# EasyEDA_export.net
KiCad netlist of a schematic drawn in EasyEDA
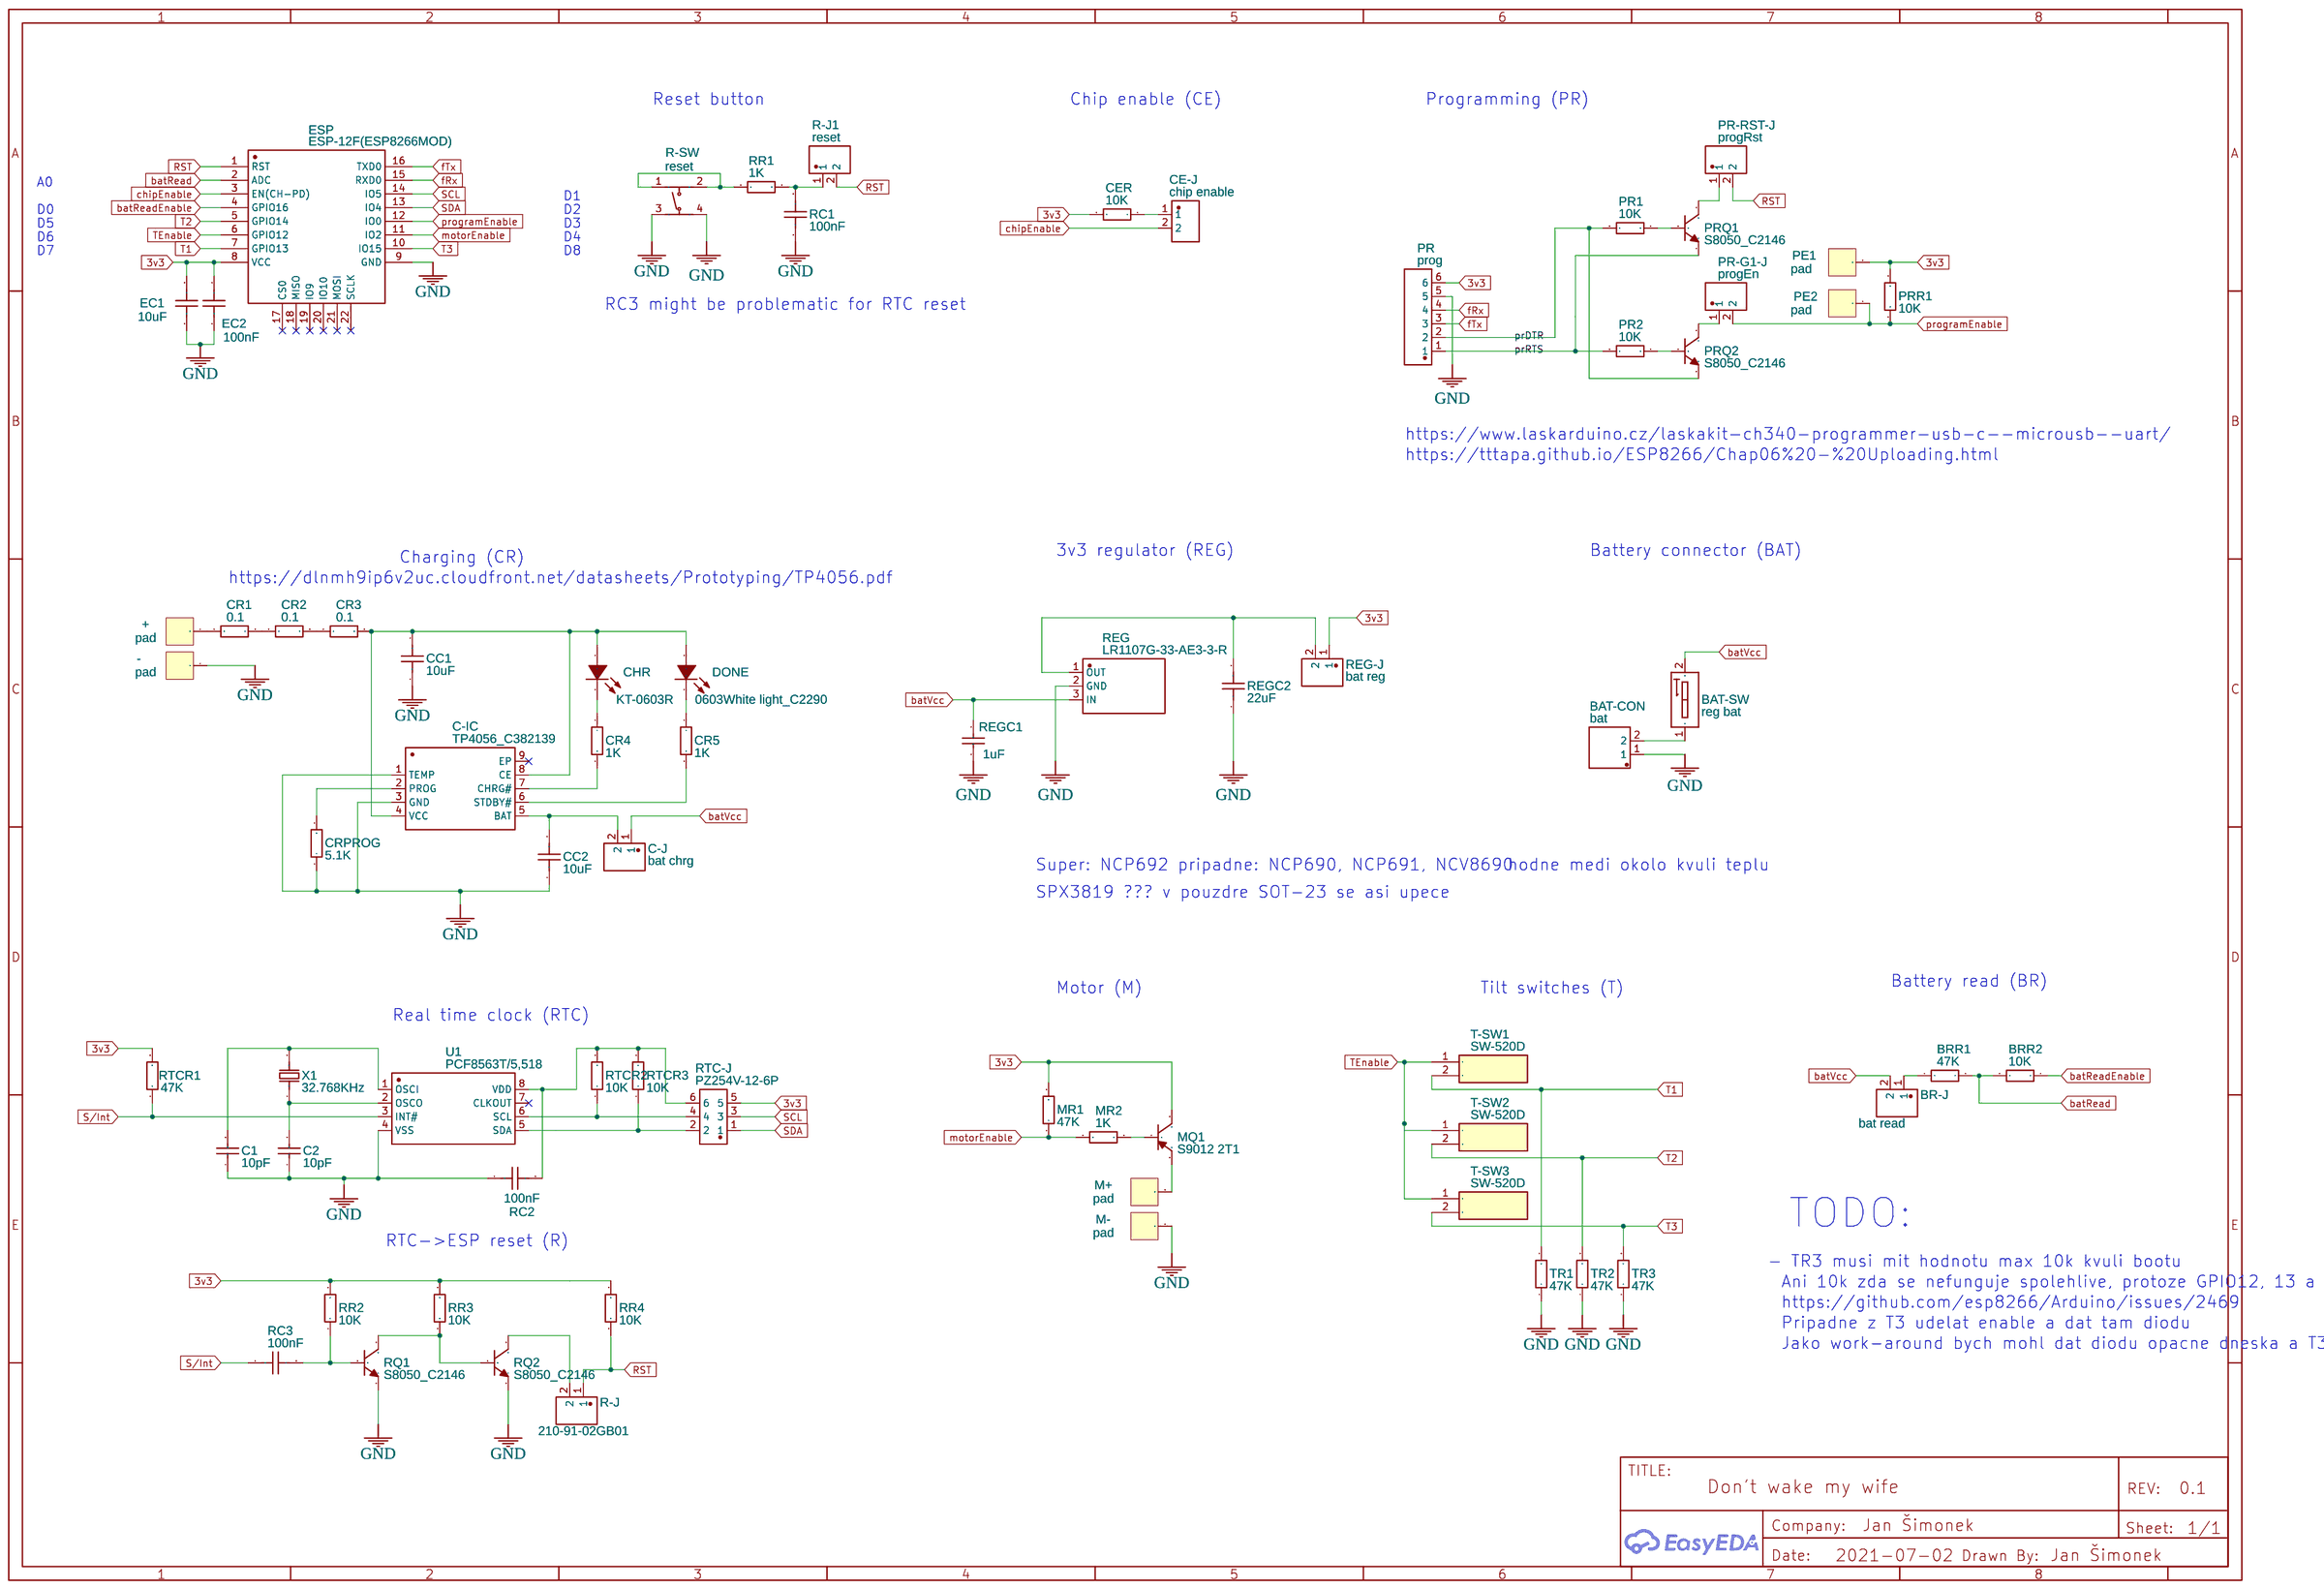
[diagram p0: schematic sheet]

(export (version "E")
  (design (tool "Eeschema 10.0.6"))
  (components
    (comp (ref "+") (value "pad") (libsource (lib "") (part "pad")))
    (comp (ref "-") (value "pad") (libsource (lib "") (part "pad_4")))
    (comp (ref "BAT-CON")
      (value "bat")
      (fields
        (field (name "BOM_Manufacturer Part") "S2B-XH-A-(LF)(SN)")
        (field (name "BOM_Supplier Part") "C157931")
      )
      (libsource (lib "") (part "S2B-XH-A-(LF)(SN)"))
    )
    (comp (ref "BAT-SW")
      (value "reg bat")
      (fields
        (field (name "BOM_Manufacturer Part") "DSIC01LSGET")
        (field (name "BOM_Supplier Part") "C54948")
      )
      (libsource (lib "") (part "DSIC01LSGET"))
    )
    (comp (ref "BR-J")
      (value "bat read")
      (fields
        (field (name "BOM_Manufacturer Part") "210-91-02GB01")
        (field (name "BOM_Supplier Part") "C390678")
      )
      (libsource (lib "") (part "210-91-02GB01"))
    )
    (comp (ref "BRR1")
      (value "47K")
      (fields
        (field (name "BOM_Manufacturer Part") "0603WAF4702T5E")
        (field (name "BOM_Supplier Part") "C25819")
      )
      (libsource (lib "") (part "0603WAF4702T5E_2"))
    )
    (comp (ref "BRR2")
      (value "10K")
      (fields
        (field (name "BOM_Manufacturer Part") "0603WAF1002T5E")
        (field (name "BOM_Supplier Part") "C25804")
      )
      (libsource (lib "") (part "0603WAF1002T5E_2"))
    )
    (comp (ref "C-IC")
      (value "TP4056_C382139")
      (fields (field (name "BOM_Manufacturer Part") "TP4056") (field (name "BOM_Supplier Part") "C382139"))
      (libsource (lib "") (part "TP4056_C382139"))
    )
    (comp (ref "C-J")
      (value "bat chrg")
      (fields
        (field (name "BOM_Manufacturer Part") "210-91-02GB01")
        (field (name "BOM_Supplier Part") "C390678")
      )
      (libsource (lib "") (part "210-91-02GB01_3"))
    )
    (comp (ref "C1")
      (value "10pF")
      (fields
        (field (name "BOM_Manufacturer Part") "CL10C100JB8NNNC")
        (field (name "BOM_Supplier Part") "C1634")
      )
      (libsource (lib "") (part "CL10C100JB8NNNC"))
    )
    (comp (ref "C2")
      (value "10pF")
      (fields
        (field (name "BOM_Manufacturer Part") "CL10C100JB8NNNC")
        (field (name "BOM_Supplier Part") "C1634")
      )
      (libsource (lib "") (part "CL10C100JB8NNNC"))
    )
    (comp (ref "CC1")
      (value "10uF")
      (fields
        (field (name "BOM_Manufacturer Part") "CL10A106KP8NNNC")
        (field (name "BOM_Supplier Part") "C19702")
      )
      (libsource (lib "") (part "CL10A106KP8NNNC_1"))
    )
    (comp (ref "CC2")
      (value "10uF")
      (fields
        (field (name "BOM_Manufacturer Part") "CL10A106KP8NNNC")
        (field (name "BOM_Supplier Part") "C19702")
      )
      (libsource (lib "") (part "CL10A106KP8NNNC_1"))
    )
    (comp (ref "CE-J")
      (value "chip enable")
      (fields
        (field (name "BOM_Manufacturer Part") "210-91-02GB01")
        (field (name "BOM_Supplier Part") "C390678")
      )
      (libsource (lib "") (part "210-91-02GB01_5"))
    )
    (comp (ref "CER")
      (value "10K")
      (fields
        (field (name "BOM_Manufacturer Part") "0603WAF1002T5E")
        (field (name "BOM_Supplier Part") "C25804")
      )
      (libsource (lib "") (part "0603WAF1002T5E_4"))
    )
    (comp (ref "CHR")
      (value "KT-0603R")
      (fields (field (name "BOM_Supplier Part") "C2286"))
      (libsource (lib "") (part "KT-0603R"))
    )
    (comp (ref "CR1")
      (value "0.1")
      (fields
        (field (name "BOM_Manufacturer Part") "0603WAJ010KT5E")
        (field (name "BOM_Supplier Part") "C247025")
      )
      (libsource (lib "") (part "0603WAJ010KT5E"))
    )
    (comp (ref "CR2")
      (value "0.1")
      (fields
        (field (name "BOM_Manufacturer Part") "0603WAJ010KT5E")
        (field (name "BOM_Supplier Part") "C247025")
      )
      (libsource (lib "") (part "0603WAJ010KT5E"))
    )
    (comp (ref "CR3")
      (value "0.1")
      (fields
        (field (name "BOM_Manufacturer Part") "0603WAJ010KT5E")
        (field (name "BOM_Supplier Part") "C247025")
      )
      (libsource (lib "") (part "0603WAJ010KT5E"))
    )
    (comp (ref "CR4")
      (value "1K")
      (fields
        (field (name "BOM_Manufacturer Part") "0603WAF1001T5E")
        (field (name "BOM_Supplier Part") "C21190")
      )
      (libsource (lib "") (part "0603WAF1001T5E"))
    )
    (comp (ref "CR5")
      (value "1K")
      (fields
        (field (name "BOM_Manufacturer Part") "0603WAF1001T5E")
        (field (name "BOM_Supplier Part") "C21190")
      )
      (libsource (lib "") (part "0603WAF1001T5E"))
    )
    (comp (ref "CRPROG")
      (value "5.1K")
      (fields
        (field (name "BOM_Manufacturer Part") "0603WAF5101T5E")
        (field (name "BOM_Supplier Part") "C23186")
      )
      (libsource (lib "") (part "0603WAF5101T5E"))
    )
    (comp (ref "DONE")
      (value "0603White light_C2290")
      (fields
        (field (name "BOM_Manufacturer Part") "0603White light")
        (field (name "BOM_Supplier Part") "C2290")
      )
      (libsource (lib "") (part "0603White light_C2290"))
    )
    (comp (ref "EC1")
      (value "10uF")
      (fields
        (field (name "BOM_Manufacturer Part") "CL10A106KP8NNNC")
        (field (name "BOM_Supplier Part") "C19702")
      )
      (libsource (lib "") (part "CL10A106KP8NNNC"))
    )
    (comp (ref "EC2")
      (value "100nF")
      (fields
        (field (name "BOM_Manufacturer Part") "CC0603KRX7R9BB104")
        (field (name "BOM_Supplier Part") "C14663")
      )
      (libsource (lib "") (part "CC0603KRX7R9BB104_2"))
    )
    (comp (ref "ESP")
      (value "ESP-12F(ESP8266MOD)")
      (fields (field (name "BOM_Supplier Part") "C82891"))
      (libsource (lib "") (part "ESP-12F(ESP8266MOD)"))
    )
    (comp (ref "M+") (value "pad") (libsource (lib "") (part "pad_1")))
    (comp (ref "M-") (value "pad") (libsource (lib "") (part "pad_3")))
    (comp (ref "MQ1")
      (value "S9012 2T1")
      (fields (field (name "BOM_Supplier Part") "C8543"))
      (libsource (lib "") (part "S9012 2T1"))
    )
    (comp (ref "MR1")
      (value "47K")
      (fields
        (field (name "BOM_Manufacturer Part") "0603WAF4702T5E")
        (field (name "BOM_Supplier Part") "C25819")
      )
      (libsource (lib "") (part "0603WAF4702T5E_3"))
    )
    (comp (ref "MR2")
      (value "1K")
      (fields
        (field (name "BOM_Manufacturer Part") "0603WAF1001T5E")
        (field (name "BOM_Supplier Part") "C21190")
      )
      (libsource (lib "") (part "0603WAF1001T5E_2"))
    )
    (comp (ref "PE1") (value "pad") (libsource (lib "") (part "pad_2")))
    (comp (ref "PE2") (value "pad") (libsource (lib "") (part "pad_2")))
    (comp (ref "PR")
      (value "prog")
      (fields
        (field (name "BOM_Manufacturer Part") "Female header 1*6p")
        (field (name "BOM_Supplier Part") "C40877")
      )
      (libsource (lib "") (part "Header-Female-2.54_1x6"))
    )
    (comp (ref "PR-G1-J")
      (value "progEn")
      (fields
        (field (name "BOM_Manufacturer Part") "210-91-02GB01")
        (field (name "BOM_Supplier Part") "C390678")
      )
      (libsource (lib "") (part "210-91-02GB01_1"))
    )
    (comp (ref "PR-RST-J")
      (value "progRst")
      (fields
        (field (name "BOM_Manufacturer Part") "210-91-02GB01")
        (field (name "BOM_Supplier Part") "C390678")
      )
      (libsource (lib "") (part "210-91-02GB01_7"))
    )
    (comp (ref "PR1")
      (value "10K")
      (fields
        (field (name "BOM_Manufacturer Part") "0603WAF1002T5E")
        (field (name "BOM_Supplier Part") "C25804")
      )
      (libsource (lib "") (part "0603WAF1002T5E"))
    )
    (comp (ref "PR2")
      (value "10K")
      (fields
        (field (name "BOM_Manufacturer Part") "0603WAF1002T5E")
        (field (name "BOM_Supplier Part") "C25804")
      )
      (libsource (lib "") (part "0603WAF1002T5E"))
    )
    (comp (ref "PRQ1")
      (value "S8050_C2146")
      (fields (field (name "BOM_Manufacturer Part") "S8050") (field (name "BOM_Supplier Part") "C2146"))
      (libsource (lib "") (part "S8050_C2146"))
    )
    (comp (ref "PRQ2")
      (value "S8050_C2146")
      (fields (field (name "BOM_Manufacturer Part") "S8050") (field (name "BOM_Supplier Part") "C2146"))
      (libsource (lib "") (part "S8050_C2146"))
    )
    (comp (ref "PRR1")
      (value "10K")
      (fields
        (field (name "BOM_Manufacturer Part") "0603WAF1002T5E")
        (field (name "BOM_Supplier Part") "C25804")
      )
      (libsource (lib "") (part "0603WAF1002T5E_5"))
    )
    (comp (ref "R-J")
      (value "210-91-02GB01")
      (fields (field (name "BOM_Supplier Part") "C390678"))
      (libsource (lib "") (part "210-91-02GB01_4"))
    )
    (comp (ref "R-J1")
      (value "reset")
      (fields
        (field (name "BOM_Manufacturer Part") "210-91-02GB01")
        (field (name "BOM_Supplier Part") "C390678")
      )
      (libsource (lib "") (part "210-91-02GB01_6"))
    )
    (comp (ref "R-SW")
      (value "reset")
      (fields
        (field (name "BOM_Manufacturer Part") "UK-B0206-G5-160-JZ")
        (field (name "BOM_Supplier Part") "C620330")
      )
      (libsource (lib "") (part "UK-B0206-G5-160-JZ"))
    )
    (comp (ref "RC1")
      (value "100nF")
      (fields
        (field (name "BOM_Manufacturer Part") "CC0603KRX7R9BB104")
        (field (name "BOM_Supplier Part") "C14663")
      )
      (libsource (lib "") (part "CC0603KRX7R9BB104"))
    )
    (comp (ref "RC2")
      (value "100nF")
      (fields
        (field (name "BOM_Manufacturer Part") "CC0603KRX7R9BB104")
        (field (name "BOM_Supplier Part") "C14663")
      )
      (libsource (lib "") (part "CC0603KRX7R9BB104_1"))
    )
    (comp (ref "RC3")
      (value "100nF")
      (fields
        (field (name "BOM_Manufacturer Part") "CC0603KRX7R9BB104")
        (field (name "BOM_Supplier Part") "C14663")
      )
      (libsource (lib "") (part "CC0603KRX7R9BB104_1"))
    )
    (comp (ref "REG")
      (value "LR1107G-33-AE3-3-R")
      (fields (field (name "BOM_Supplier Part") "C171497"))
      (libsource (lib "") (part "LR1107G-33-AE3-3-R"))
    )
    (comp (ref "REG-J")
      (value "bat reg")
      (fields
        (field (name "BOM_Manufacturer Part") "210-91-02GB01")
        (field (name "BOM_Supplier Part") "C390678")
      )
      (libsource (lib "") (part "210-91-02GB01_2"))
    )
    (comp (ref "REGC1")
      (value "1uF")
      (fields
        (field (name "BOM_Manufacturer Part") "CL10A105KB8NNNC")
        (field (name "BOM_Supplier Part") "C15849")
      )
      (libsource (lib "") (part "CL10A105KB8NNNC"))
    )
    (comp (ref "REGC2")
      (value "22uF")
      (fields
        (field (name "BOM_Manufacturer Part") "CL10A226MQ8NRNC")
        (field (name "BOM_Supplier Part") "C59461")
      )
      (libsource (lib "") (part "CL10A226MQ8NRNC"))
    )
    (comp (ref "RQ1")
      (value "S8050_C2146")
      (fields (field (name "BOM_Manufacturer Part") "S8050") (field (name "BOM_Supplier Part") "C2146"))
      (libsource (lib "") (part "S8050_C2146_1"))
    )
    (comp (ref "RQ2")
      (value "S8050_C2146")
      (fields (field (name "BOM_Manufacturer Part") "S8050") (field (name "BOM_Supplier Part") "C2146"))
      (libsource (lib "") (part "S8050_C2146_1"))
    )
    (comp (ref "RR1")
      (value "1K")
      (fields
        (field (name "BOM_Manufacturer Part") "0603WAF1001T5E")
        (field (name "BOM_Supplier Part") "C21190")
      )
      (libsource (lib "") (part "0603WAF1001T5E_1"))
    )
    (comp (ref "RR2")
      (value "10K")
      (fields
        (field (name "BOM_Manufacturer Part") "0603WAF1002T5E")
        (field (name "BOM_Supplier Part") "C25804")
      )
      (libsource (lib "") (part "0603WAF1002T5E_3"))
    )
    (comp (ref "RR3")
      (value "10K")
      (fields
        (field (name "BOM_Manufacturer Part") "0603WAF1002T5E")
        (field (name "BOM_Supplier Part") "C25804")
      )
      (libsource (lib "") (part "0603WAF1002T5E_3"))
    )
    (comp (ref "RR4")
      (value "10K")
      (fields
        (field (name "BOM_Manufacturer Part") "0603WAF1002T5E")
        (field (name "BOM_Supplier Part") "C25804")
      )
      (libsource (lib "") (part "0603WAF1002T5E_3"))
    )
    (comp (ref "RTC-J")
      (value "PZ254V-12-6P")
      (fields (field (name "BOM_Supplier Part") "C492420"))
      (libsource (lib "") (part "PZ254V-12-6P"))
    )
    (comp (ref "RTCR1")
      (value "47K")
      (fields
        (field (name "BOM_Manufacturer Part") "0603WAF4702T5E")
        (field (name "BOM_Supplier Part") "C25819")
      )
      (libsource (lib "") (part "0603WAF4702T5E"))
    )
    (comp (ref "RTCR2")
      (value "10K")
      (fields
        (field (name "BOM_Manufacturer Part") "0603WAF1002T5E")
        (field (name "BOM_Supplier Part") "C25804")
      )
      (libsource (lib "") (part "0603WAF1002T5E_1"))
    )
    (comp (ref "RTCR3")
      (value "10K")
      (fields
        (field (name "BOM_Manufacturer Part") "0603WAF1002T5E")
        (field (name "BOM_Supplier Part") "C25804")
      )
      (libsource (lib "") (part "0603WAF1002T5E_1"))
    )
    (comp (ref "T-SW1") (value "SW-520D") (libsource (lib "") (part "SW-520D")))
    (comp (ref "T-SW2") (value "SW-520D") (libsource (lib "") (part "SW-520D")))
    (comp (ref "T-SW3") (value "SW-520D") (libsource (lib "") (part "SW-520D")))
    (comp (ref "TR1")
      (value "47K")
      (fields
        (field (name "BOM_Manufacturer Part") "0603WAF4702T5E")
        (field (name "BOM_Supplier Part") "C25819")
      )
      (libsource (lib "") (part "0603WAF4702T5E_1"))
    )
    (comp (ref "TR2")
      (value "47K")
      (fields
        (field (name "BOM_Manufacturer Part") "0603WAF4702T5E")
        (field (name "BOM_Supplier Part") "C25819")
      )
      (libsource (lib "") (part "0603WAF4702T5E_1"))
    )
    (comp (ref "TR3")
      (value "47K")
      (fields
        (field (name "BOM_Manufacturer Part") "0603WAF4702T5E")
        (field (name "BOM_Supplier Part") "C25819")
      )
      (libsource (lib "") (part "0603WAF4702T5E_1"))
    )
    (comp (ref "U1")
      (value "PCF8563T/5,518")
      (fields (field (name "BOM_Supplier Part") "C7440"))
      (libsource (lib "") (part "PCF8563T/5,518"))
    )
    (comp (ref "X1")
      (value "32.768KHz")
      (fields
        (field (name "BOM_Manufacturer Part") "Q13FC1350000400")
        (field (name "BOM_Supplier Part") "C32346")
      )
      (libsource (lib "") (part "Q13FC1350000400"))
    )
  )
  (nets
    (net (code "1") (name "/prDTR") (class "Default")
      (node (ref "PR") (pin "2") (pinfunction "2_2") (pintype "unspecified"))
      (node (ref "PR1") (pin "2") (pinfunction "2_2") (pintype "input"))
      (node (ref "PRQ2") (pin "2") (pinfunction "E_2") (pintype "unspecified"))
    )
    (net (code "2") (name "/prRTS") (class "Default")
      (node (ref "PR") (pin "1") (pinfunction "1_1") (pintype "unspecified"))
      (node (ref "PR2") (pin "2") (pinfunction "2_2") (pintype "input"))
      (node (ref "PRQ1") (pin "2") (pinfunction "E_2") (pintype "unspecified"))
    )
    (net (code "3") (name "3v3") (class "Default")
      (node (ref "CER") (pin "2") (pinfunction "2_2") (pintype "input"))
      (node (ref "EC1") (pin "2") (pinfunction "2_2") (pintype "unspecified"))
      (node (ref "EC2") (pin "2") (pinfunction "2_2") (pintype "unspecified"))
      (node (ref "ESP") (pin "8") (pinfunction "VCC_8") (pintype "unspecified"))
      (node (ref "MQ1") (pin "3") (pinfunction "C_3") (pintype "unspecified"))
      (node (ref "MR1") (pin "2") (pinfunction "2_2") (pintype "input"))
      (node (ref "PE1") (pin "1") (pinfunction "1_1") (pintype "unspecified"))
      (node (ref "PR") (pin "6") (pinfunction "6_6") (pintype "unspecified"))
      (node (ref "PRR1") (pin "2") (pinfunction "2_2") (pintype "input"))
      (node (ref "REG-J") (pin "1") (pinfunction "1_1") (pintype "unspecified"))
      (node (ref "RR2") (pin "2") (pinfunction "2_2") (pintype "input"))
      (node (ref "RR3") (pin "2") (pinfunction "2_2") (pintype "input"))
      (node (ref "RR4") (pin "2") (pinfunction "2_2") (pintype "input"))
      (node (ref "RTC-J") (pin "5") (pinfunction "5_5") (pintype "unspecified"))
      (node (ref "RTCR1") (pin "2") (pinfunction "2_2") (pintype "input"))
    )
    (net (code "4") (name "GND") (class "Default")
      (node (ref "-") (pin "1") (pinfunction "1_1") (pintype "unspecified"))
      (node (ref "BAT-CON") (pin "1") (pinfunction "1_1") (pintype "unspecified"))
      (node (ref "C-IC") (pin "1") (pinfunction "TEMP_1") (pintype "unspecified"))
      (node (ref "C-IC") (pin "3") (pinfunction "GND_3") (pintype "unspecified"))
      (node (ref "C1") (pin "1") (pinfunction "1_1") (pintype "input"))
      (node (ref "C2") (pin "1") (pinfunction "1_1") (pintype "input"))
      (node (ref "CC1") (pin "1") (pinfunction "1_1") (pintype "unspecified"))
      (node (ref "CC2") (pin "1") (pinfunction "1_1") (pintype "unspecified"))
      (node (ref "CRPROG") (pin "1") (pinfunction "1_1") (pintype "input"))
      (node (ref "EC1") (pin "1") (pinfunction "1_1") (pintype "unspecified"))
      (node (ref "EC2") (pin "1") (pinfunction "1_1") (pintype "unspecified"))
      (node (ref "ESP") (pin "9") (pinfunction "GND_9") (pintype "unspecified"))
      (node (ref "M-") (pin "1") (pinfunction "1_1") (pintype "unspecified"))
      (node (ref "PR") (pin "5") (pinfunction "5_5") (pintype "unspecified"))
      (node (ref "R-SW") (pin "3") (pinfunction "3_3") (pintype "unspecified"))
      (node (ref "R-SW") (pin "4") (pinfunction "4_4") (pintype "unspecified"))
      (node (ref "RC1") (pin "1") (pinfunction "1_1") (pintype "unspecified"))
      (node (ref "RC2") (pin "1") (pinfunction "1_1") (pintype "unspecified"))
      (node (ref "REG") (pin "2") (pinfunction "GND_2") (pintype "unspecified"))
      (node (ref "REGC1") (pin "1") (pinfunction "1_1") (pintype "input"))
      (node (ref "REGC2") (pin "1") (pinfunction "1_1") (pintype "unspecified"))
      (node (ref "RQ1") (pin "2") (pinfunction "E_2") (pintype "unspecified"))
      (node (ref "RQ2") (pin "2") (pinfunction "E_2") (pintype "unspecified"))
      (node (ref "TR1") (pin "1") (pinfunction "1_1") (pintype "input"))
      (node (ref "TR2") (pin "1") (pinfunction "1_1") (pintype "input"))
      (node (ref "TR3") (pin "1") (pinfunction "1_1") (pintype "input"))
      (node (ref "U1") (pin "4") (pinfunction "VSS_4") (pintype "unspecified"))
    )
    (net (code "5") (name "Net-(+-Pad1)") (class "Default")
      (node (ref "+") (pin "1") (pinfunction "1_1") (pintype "unspecified"))
      (node (ref "CR1") (pin "1") (pinfunction "1_1") (pintype "unspecified"))
    )
    (net (code "6") (name "Net-(BAT-SW-A1)") (class "Default")
      (node (ref "BAT-CON") (pin "2") (pinfunction "2_2") (pintype "unspecified"))
      (node (ref "BAT-SW") (pin "1") (pinfunction "A1_1") (pintype "input"))
    )
    (net (code "7") (name "Net-(BR-J-Pad1)") (class "Default")
      (node (ref "BR-J") (pin "1") (pinfunction "1_1") (pintype "unspecified"))
      (node (ref "BRR1") (pin "1") (pinfunction "1_1") (pintype "input"))
    )
    (net (code "8") (name "Net-(C-IC-BAT)") (class "Default")
      (node (ref "C-IC") (pin "5") (pinfunction "BAT_5") (pintype "unspecified"))
      (node (ref "C-J") (pin "2") (pinfunction "2_2") (pintype "unspecified"))
      (node (ref "CC2") (pin "2") (pinfunction "2_2") (pintype "unspecified"))
    )
    (net (code "9") (name "Net-(C-IC-CE)") (class "Default")
      (node (ref "C-IC") (pin "4") (pinfunction "VCC_4") (pintype "unspecified"))
      (node (ref "C-IC") (pin "8") (pinfunction "CE_8") (pintype "unspecified"))
      (node (ref "CC1") (pin "2") (pinfunction "2_2") (pintype "unspecified"))
      (node (ref "CHR") (pin "1") (pinfunction "A_1") (pintype "unspecified"))
      (node (ref "CR3") (pin "2") (pinfunction "2_2") (pintype "unspecified"))
      (node (ref "DONE") (pin "1") (pinfunction "A_1") (pintype "unspecified"))
    )
    (net (code "10") (name "Net-(C-IC-CHRG#)") (class "Default")
      (node (ref "C-IC") (pin "7") (pinfunction "CHRG#_7") (pintype "unspecified"))
      (node (ref "CR4") (pin "2") (pinfunction "2_2") (pintype "input"))
    )
    (net (code "11") (name "Net-(C-IC-PROG)") (class "Default")
      (node (ref "C-IC") (pin "2") (pinfunction "PROG_2") (pintype "unspecified"))
      (node (ref "CRPROG") (pin "2") (pinfunction "2_2") (pintype "input"))
    )
    (net (code "12") (name "Net-(C-IC-STDBY#)") (class "Default")
      (node (ref "C-IC") (pin "6") (pinfunction "STDBY#_6") (pintype "unspecified"))
      (node (ref "CR5") (pin "2") (pinfunction "2_2") (pintype "input"))
    )
    (net (code "13") (name "Net-(CE-J-Pad1)") (class "Default")
      (node (ref "CE-J") (pin "1") (pinfunction "1_1") (pintype "unspecified"))
      (node (ref "CER") (pin "1") (pinfunction "1_1") (pintype "input"))
    )
    (net (code "14") (name "Net-(CHR-K)") (class "Default")
      (node (ref "CHR") (pin "2") (pinfunction "K_2") (pintype "unspecified"))
      (node (ref "CR4") (pin "1") (pinfunction "1_1") (pintype "input"))
    )
    (net (code "15") (name "Net-(CR1-Pad2)") (class "Default")
      (node (ref "CR1") (pin "2") (pinfunction "2_2") (pintype "unspecified"))
      (node (ref "CR2") (pin "1") (pinfunction "1_1") (pintype "unspecified"))
    )
    (net (code "16") (name "Net-(CR2-Pad2)") (class "Default")
      (node (ref "CR2") (pin "2") (pinfunction "2_2") (pintype "unspecified"))
      (node (ref "CR3") (pin "1") (pinfunction "1_1") (pintype "unspecified"))
    )
    (net (code "17") (name "Net-(DONE-K)") (class "Default")
      (node (ref "CR5") (pin "1") (pinfunction "1_1") (pintype "input"))
      (node (ref "DONE") (pin "2") (pinfunction "K_2") (pintype "unspecified"))
    )
    (net (code "18") (name "Net-(MQ1-B)") (class "Default")
      (node (ref "MQ1") (pin "1") (pinfunction "B_1") (pintype "unspecified"))
      (node (ref "MR2") (pin "2") (pinfunction "2_2") (pintype "input"))
    )
    (net (code "19") (name "Net-(MQ1-E)") (class "Default")
      (node (ref "M+") (pin "1") (pinfunction "1_1") (pintype "unspecified"))
      (node (ref "MQ1") (pin "2") (pinfunction "E_2") (pintype "unspecified"))
    )
    (net (code "20") (name "Net-(PRQ1-B)") (class "Default")
      (node (ref "PR1") (pin "1") (pinfunction "1_1") (pintype "input"))
      (node (ref "PRQ1") (pin "1") (pinfunction "B_1") (pintype "unspecified"))
    )
    (net (code "21") (name "Net-(PRQ1-C)") (class "Default")
      (node (ref "PR-RST-J") (pin "1") (pinfunction "1_1") (pintype "unspecified"))
      (node (ref "PRQ1") (pin "3") (pinfunction "C_3") (pintype "unspecified"))
    )
    (net (code "22") (name "Net-(PRQ2-B)") (class "Default")
      (node (ref "PR2") (pin "1") (pinfunction "1_1") (pintype "input"))
      (node (ref "PRQ2") (pin "1") (pinfunction "B_1") (pintype "unspecified"))
    )
    (net (code "23") (name "Net-(PRQ2-C)") (class "Default")
      (node (ref "PR-G1-J") (pin "1") (pinfunction "1_1") (pintype "unspecified"))
      (node (ref "PRQ2") (pin "3") (pinfunction "C_3") (pintype "unspecified"))
    )
    (net (code "24") (name "Net-(R-J1-Pad1)") (class "Default")
      (node (ref "R-J1") (pin "1") (pinfunction "1_1") (pintype "unspecified"))
      (node (ref "RC1") (pin "2") (pinfunction "2_2") (pintype "unspecified"))
      (node (ref "RR1") (pin "2") (pinfunction "2_2") (pintype "input"))
    )
    (net (code "25") (name "Net-(R-SW-Pad1)") (class "Default")
      (node (ref "R-SW") (pin "1") (pinfunction "1_1") (pintype "unspecified"))
      (node (ref "R-SW") (pin "2") (pinfunction "2_2") (pintype "unspecified"))
      (node (ref "RR1") (pin "1") (pinfunction "1_1") (pintype "input"))
    )
    (net (code "26") (name "Net-(REG-OUT)") (class "Default")
      (node (ref "REG") (pin "1") (pinfunction "OUT_1") (pintype "unspecified"))
      (node (ref "REG-J") (pin "2") (pinfunction "2_2") (pintype "unspecified"))
      (node (ref "REGC2") (pin "2") (pinfunction "2_2") (pintype "unspecified"))
    )
    (net (code "27") (name "Net-(RQ1-B)") (class "Default")
      (node (ref "RC3") (pin "2") (pinfunction "2_2") (pintype "unspecified"))
      (node (ref "RQ1") (pin "1") (pinfunction "B_1") (pintype "unspecified"))
      (node (ref "RR2") (pin "1") (pinfunction "1_1") (pintype "input"))
    )
    (net (code "28") (name "Net-(RQ1-C)") (class "Default")
      (node (ref "RQ1") (pin "3") (pinfunction "C_3") (pintype "unspecified"))
      (node (ref "RQ2") (pin "1") (pinfunction "B_1") (pintype "unspecified"))
      (node (ref "RR3") (pin "1") (pinfunction "1_1") (pintype "input"))
    )
    (net (code "29") (name "Net-(RQ2-C)") (class "Default")
      (node (ref "R-J") (pin "2") (pinfunction "2_2") (pintype "unspecified"))
      (node (ref "RQ2") (pin "3") (pinfunction "C_3") (pintype "unspecified"))
    )
    (net (code "30") (name "Net-(U1-OSCI)") (class "Default")
      (node (ref "C1") (pin "2") (pinfunction "2_2") (pintype "input"))
      (node (ref "U1") (pin "1") (pinfunction "OSCI_1") (pintype "unspecified"))
      (node (ref "X1") (pin "2") (pinfunction "2_2") (pintype "unspecified"))
    )
    (net (code "31") (name "Net-(U1-OSCO)") (class "Default")
      (node (ref "C2") (pin "2") (pinfunction "2_2") (pintype "input"))
      (node (ref "U1") (pin "2") (pinfunction "OSCO_2") (pintype "unspecified"))
      (node (ref "X1") (pin "1") (pinfunction "1_1") (pintype "unspecified"))
    )
    (net (code "32") (name "Net-(U1-SCL)") (class "Default")
      (node (ref "RTC-J") (pin "4") (pinfunction "4_4") (pintype "unspecified"))
      (node (ref "RTCR2") (pin "1") (pinfunction "1_1") (pintype "input"))
      (node (ref "U1") (pin "6") (pinfunction "SCL_6") (pintype "unspecified"))
    )
    (net (code "33") (name "Net-(U1-SDA)") (class "Default")
      (node (ref "RTC-J") (pin "2") (pinfunction "2_2") (pintype "unspecified"))
      (node (ref "RTCR3") (pin "1") (pinfunction "1_1") (pintype "input"))
      (node (ref "U1") (pin "5") (pinfunction "SDA_5") (pintype "unspecified"))
    )
    (net (code "34") (name "Net-(U1-VDD)") (class "Default")
      (node (ref "RC2") (pin "2") (pinfunction "2_2") (pintype "unspecified"))
      (node (ref "RTC-J") (pin "6") (pinfunction "6_6") (pintype "unspecified"))
      (node (ref "RTCR2") (pin "2") (pinfunction "2_2") (pintype "input"))
      (node (ref "RTCR3") (pin "2") (pinfunction "2_2") (pintype "input"))
      (node (ref "U1") (pin "8") (pinfunction "VDD_8") (pintype "unspecified"))
    )
    (net (code "35") (name "RST") (class "Default")
      (node (ref "ESP") (pin "1") (pinfunction "RST_1") (pintype "unspecified"))
      (node (ref "PR-RST-J") (pin "2") (pinfunction "2_2") (pintype "unspecified"))
      (node (ref "R-J") (pin "1") (pinfunction "1_1") (pintype "unspecified"))
      (node (ref "R-J1") (pin "2") (pinfunction "2_2") (pintype "unspecified"))
      (node (ref "RR4") (pin "1") (pinfunction "1_1") (pintype "input"))
    )
    (net (code "36") (name "SCL") (class "Default")
      (node (ref "ESP") (pin "14") (pinfunction "IO5_14") (pintype "unspecified"))
      (node (ref "RTC-J") (pin "3") (pinfunction "3_3") (pintype "unspecified"))
    )
    (net (code "37") (name "SDA") (class "Default")
      (node (ref "ESP") (pin "13") (pinfunction "IO4_13") (pintype "unspecified"))
      (node (ref "RTC-J") (pin "1") (pinfunction "1_1") (pintype "unspecified"))
    )
    (net (code "38") (name "S{slash}Int") (class "Default")
      (node (ref "RC3") (pin "1") (pinfunction "1_1") (pintype "unspecified"))
      (node (ref "RTCR1") (pin "1") (pinfunction "1_1") (pintype "input"))
      (node (ref "U1") (pin "3") (pinfunction "INT#_3") (pintype "unspecified"))
    )
    (net (code "39") (name "T1") (class "Default")
      (node (ref "ESP") (pin "7") (pinfunction "GPIO13_7") (pintype "unspecified"))
      (node (ref "T-SW1") (pin "2") (pinfunction "2_2") (pintype "unspecified"))
      (node (ref "TR1") (pin "2") (pinfunction "2_2") (pintype "input"))
    )
    (net (code "40") (name "T2") (class "Default")
      (node (ref "ESP") (pin "5") (pinfunction "GPIO14_5") (pintype "unspecified"))
      (node (ref "T-SW2") (pin "2") (pinfunction "2_2") (pintype "unspecified"))
      (node (ref "TR2") (pin "2") (pinfunction "2_2") (pintype "input"))
    )
    (net (code "41") (name "T3") (class "Default")
      (node (ref "ESP") (pin "10") (pinfunction "IO15_10") (pintype "unspecified"))
      (node (ref "T-SW3") (pin "2") (pinfunction "2_2") (pintype "unspecified"))
      (node (ref "TR3") (pin "2") (pinfunction "2_2") (pintype "input"))
    )
    (net (code "42") (name "TEnable") (class "Default")
      (node (ref "ESP") (pin "6") (pinfunction "GPIO12_6") (pintype "unspecified"))
      (node (ref "T-SW1") (pin "1") (pinfunction "1_1") (pintype "unspecified"))
      (node (ref "T-SW2") (pin "1") (pinfunction "1_1") (pintype "unspecified"))
      (node (ref "T-SW3") (pin "1") (pinfunction "1_1") (pintype "unspecified"))
    )
    (net (code "43") (name "batRead") (class "Default")
      (node (ref "BRR1") (pin "2") (pinfunction "2_2") (pintype "input"))
      (node (ref "BRR2") (pin "2") (pinfunction "2_2") (pintype "input"))
      (node (ref "ESP") (pin "2") (pinfunction "ADC_2") (pintype "unspecified"))
    )
    (net (code "44") (name "batReadEnable") (class "Default")
      (node (ref "BRR2") (pin "1") (pinfunction "1_1") (pintype "input"))
      (node (ref "ESP") (pin "4") (pinfunction "GPIO16_4") (pintype "unspecified"))
    )
    (net (code "45") (name "batVcc") (class "Default")
      (node (ref "BAT-SW") (pin "2") (pinfunction "A2_2") (pintype "input"))
      (node (ref "BR-J") (pin "2") (pinfunction "2_2") (pintype "unspecified"))
      (node (ref "C-J") (pin "1") (pinfunction "1_1") (pintype "unspecified"))
      (node (ref "REG") (pin "3") (pinfunction "IN_3") (pintype "unspecified"))
      (node (ref "REGC1") (pin "2") (pinfunction "2_2") (pintype "input"))
    )
    (net (code "46") (name "chipEnable") (class "Default")
      (node (ref "CE-J") (pin "2") (pinfunction "2_2") (pintype "unspecified"))
      (node (ref "ESP") (pin "3") (pinfunction "EN(CH-PD)_3") (pintype "unspecified"))
    )
    (net (code "47") (name "fRx") (class "Default")
      (node (ref "ESP") (pin "15") (pinfunction "RXD0_15") (pintype "unspecified"))
      (node (ref "PR") (pin "4") (pinfunction "4_4") (pintype "unspecified"))
    )
    (net (code "48") (name "fTx") (class "Default")
      (node (ref "ESP") (pin "16") (pinfunction "TXD0_16") (pintype "unspecified"))
      (node (ref "PR") (pin "3") (pinfunction "3_3") (pintype "unspecified"))
    )
    (net (code "49") (name "motorEnable") (class "Default")
      (node (ref "ESP") (pin "11") (pinfunction "IO2_11") (pintype "unspecified"))
      (node (ref "MR1") (pin "1") (pinfunction "1_1") (pintype "input"))
      (node (ref "MR2") (pin "1") (pinfunction "1_1") (pintype "input"))
    )
    (net (code "50") (name "programEnable") (class "Default")
      (node (ref "ESP") (pin "12") (pinfunction "IO0_12") (pintype "unspecified"))
      (node (ref "PE2") (pin "1") (pinfunction "1_1") (pintype "unspecified"))
      (node (ref "PR-G1-J") (pin "2") (pinfunction "2_2") (pintype "unspecified"))
      (node (ref "PRR1") (pin "1") (pinfunction "1_1") (pintype "input"))
    )
    (net (code "51") (name "unconnected-(C-IC-EP-Pad9)") (class "Default")
      (node (ref "C-IC") (pin "9") (pinfunction "EP_9") (pintype "unspecified+no_connect"))
    )
    (net (code "52") (name "unconnected-(ESP-CS0-Pad17)") (class "Default")
      (node (ref "ESP") (pin "17") (pinfunction "CS0_17") (pintype "unspecified+no_connect"))
    )
    (net (code "53") (name "unconnected-(ESP-IO9-Pad19)") (class "Default")
      (node (ref "ESP") (pin "19") (pinfunction "IO9_19") (pintype "unspecified+no_connect"))
    )
    (net (code "54") (name "unconnected-(ESP-IO10-Pad20)") (class "Default")
      (node (ref "ESP") (pin "20") (pinfunction "IO10_20") (pintype "unspecified+no_connect"))
    )
    (net (code "55") (name "unconnected-(ESP-MISO-Pad18)") (class "Default")
      (node (ref "ESP") (pin "18") (pinfunction "MISO_18") (pintype "unspecified+no_connect"))
    )
    (net (code "56") (name "unconnected-(ESP-MOSI-Pad21)") (class "Default")
      (node (ref "ESP") (pin "21") (pinfunction "MOSI_21") (pintype "unspecified+no_connect"))
    )
    (net (code "57") (name "unconnected-(ESP-SCLK-Pad22)") (class "Default")
      (node (ref "ESP") (pin "22") (pinfunction "SCLK_22") (pintype "unspecified+no_connect"))
    )
    (net (code "58") (name "unconnected-(U1-CLKOUT-Pad7)") (class "Default")
      (node (ref "U1") (pin "7") (pinfunction "CLKOUT_7") (pintype "unspecified+no_connect"))
    )
  )
)
